# Low_Pass_Filter_Destama.net
KiCad netlist of a schematic drawn in EAGLE
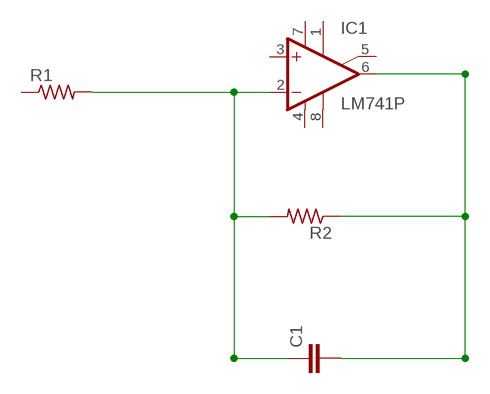
[diagram p0: schematic, sheet 1]

(export (version "E")
  (design (tool "Eeschema 10.0.6"))
  (components
    (comp (ref "C1")
      (value "C2.5/2")
      (footprint "eagle-import:C2.5-2")
      (libsource (lib "eagle-import") (part "C2.5/2"))
    )
    (comp (ref "IC1")
      (value "LM741P")
      (footprint "eagle-import:DIL08")
      (libsource (lib "eagle-import") (part "741PLM"))
    )
    (comp (ref "R1")
      (value "R-US_0204/7")
      (footprint "eagle-import:0204_7")
      (libsource (lib "eagle-import") (part "R-US_0204/7"))
    )
    (comp (ref "R2")
      (value "R-US_0204/7")
      (footprint "eagle-import:0204_7")
      (libsource (lib "eagle-import") (part "R-US_0204/7"))
    )
  )
  (nets
    (net (code "1") (name "/V+") (class "Default")
      (node (ref "IC1") (pin "7") (pinfunction "V+_7") (pintype "power_in"))
    )
    (net (code "2") (name "/V-") (class "Default")
      (node (ref "IC1") (pin "4") (pinfunction "V-_4") (pintype "power_in"))
    )
    (net (code "3") (name "Net-(IC1--IN)") (class "Default")
      (node (ref "C1") (pin "1") (pinfunction "1_1") (pintype "passive"))
      (node (ref "IC1") (pin "2") (pinfunction "-IN_2") (pintype "input"))
      (node (ref "R1") (pin "2") (pinfunction "2_2") (pintype "passive"))
      (node (ref "R2") (pin "2") (pinfunction "2_2") (pintype "passive"))
    )
    (net (code "4") (name "Net-(IC1-OUT)") (class "Default")
      (node (ref "C1") (pin "2") (pinfunction "2_2") (pintype "passive"))
      (node (ref "IC1") (pin "6") (pinfunction "OUT_6") (pintype "output"))
      (node (ref "R2") (pin "1") (pinfunction "1_1") (pintype "passive"))
    )
    (net (code "5") (name "unconnected-(IC1-+IN-Pad3)") (class "Default")
      (node (ref "IC1") (pin "3") (pinfunction "+IN_3") (pintype "input"))
    )
    (net (code "6") (name "unconnected-(IC1-ON1-Pad1)") (class "Default")
      (node (ref "IC1") (pin "1") (pinfunction "ON1_1") (pintype "passive"))
    )
    (net (code "7") (name "unconnected-(IC1-ON2-Pad5)") (class "Default")
      (node (ref "IC1") (pin "5") (pinfunction "ON2_5") (pintype "passive"))
    )
    (net (code "8") (name "unconnected-(IC1-OPT-Pad8)") (class "Default")
      (node (ref "IC1") (pin "8") (pinfunction "OPT_8") (pintype "passive"))
    )
    (net (code "9") (name "unconnected-(R1-Pad1)") (class "Default")
      (node (ref "R1") (pin "1") (pinfunction "1_1") (pintype "passive"))
    )
  )
)
